# team_back_ECU.net
KiCad netlist of a schematic drawn in Altium Designer
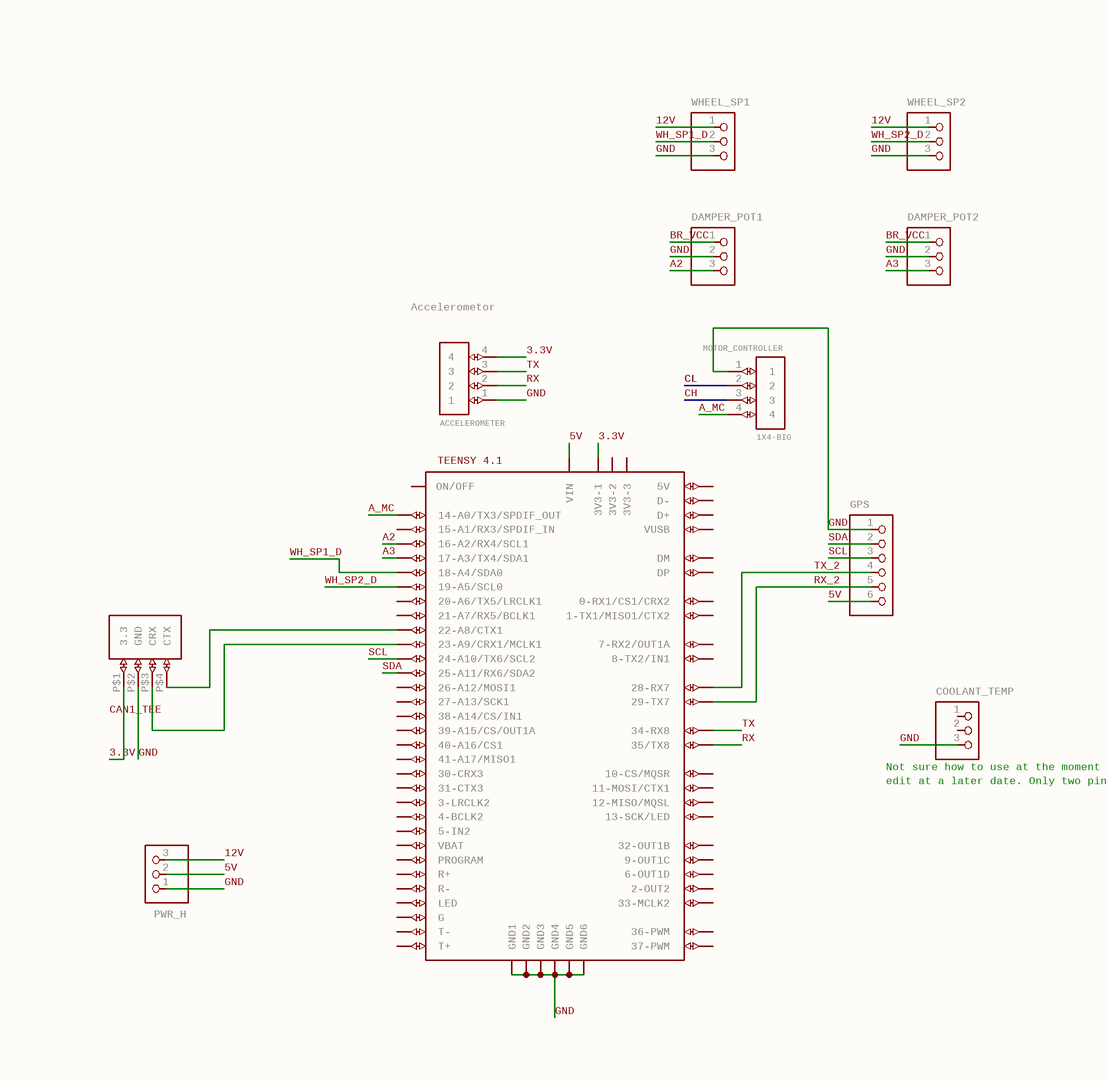
[diagram p0: team back ECU.SchDoc]

(export (version "E")
  (design (tool "Eeschema 10.0.6"))
  (components
    (comp (ref "ACCELEROMETER")
      (value "~")
      (footprint "1X04-3.5MM")
      (description "4-pin connector")
      (fields (field (name "AC") "Accelerometor"))
      (libsource (lib "adafruit") (part "1X4-3.5MM"))
    )
    (comp (ref "CAN1_TEE")
      (value "~")
      (footprint "CAN_TEN")
      (libsource (lib "F-E library custom components") (part "CAN_TEE"))
    )
    (comp (ref "COOLANT_TEMP")
      (value "~")
      (footprint "1X03")
      (description "PIN HEADER")
      (libsource (lib "adafruit") (part "PINHD-1X3"))
    )
    (comp (ref "DAMPER_POT1")
      (value "~")
      (footprint "1X03-CLEANBIG")
      (description "PIN HEADER")
      (libsource (lib "adafruit") (part "PINHD-1X3CB"))
    )
    (comp (ref "DAMPER_POT2")
      (value "~")
      (footprint "1X03-CLEANBIG")
      (description "PIN HEADER")
      (libsource (lib "adafruit") (part "PINHD-1X3CB"))
    )
    (comp (ref "GPS")
      (value "~")
      (footprint "1X06-3.5MM")
      (description "PIN HEADER")
      (libsource (lib "adafruit") (part "PINHD-1X6-3.5MM"))
    )
    (comp (ref "MOTOR_CONTROLLER")
      (value "1X4-BIG")
      (footprint "1X04-BIG")
      (description "4-pin connector")
      (libsource (lib "adafruit") (part "1X4-BIG"))
    )
    (comp (ref "PWR_H")
      (value "~")
      (footprint "1X03")
      (description "PIN HEADER")
      (libsource (lib "adafruit") (part "PINHD-1X3"))
    )
    (comp (ref "U$1")
      (value "~")
      (footprint "TEENSY41")
      (fields (field (name "TEENSY4.1") "TEENSY 4.1"))
      (libsource (lib "teensy") (part "TEENSY41"))
    )
    (comp (ref "WHEEL_SP1")
      (value "~")
      (footprint "1X03")
      (description "PIN HEADER")
      (libsource (lib "adafruit") (part "PINHD-1X3"))
    )
    (comp (ref "WHEEL_SP2")
      (value "~")
      (footprint "1X03")
      (description "PIN HEADER")
      (libsource (lib "adafruit") (part "PINHD-1X3"))
    )
  )
  (nets
    (net (code "3") (name "/3.3V") (class "Default")
      (node (ref "ACCELEROMETER") (pin "4") (pinfunction "4_4") (pintype "bidirectional"))
      (node (ref "CAN1_TEE") (pin "P$1") (pinfunction "3.3_P$1") (pintype "bidirectional"))
      (node (ref "U$1") (pin "3V3-1") (pinfunction "3V3-1_3V3-1") (pintype "bidirectional"))
    )
    (net (code "4") (name "/5V") (class "Default")
      (node (ref "GPS") (pin "6") (pinfunction "6_6") (pintype "passive"))
      (node (ref "PWR_H") (pin "2") (pinfunction "2_2") (pintype "passive"))
      (node (ref "U$1") (pin "VIN") (pinfunction "VIN_VIN") (pintype "bidirectional"))
    )
    (net (code "5") (name "/12V") (class "Default")
      (node (ref "PWR_H") (pin "3") (pinfunction "3_3") (pintype "passive"))
      (node (ref "WHEEL_SP1") (pin "1") (pinfunction "1_1") (pintype "passive"))
      (node (ref "WHEEL_SP2") (pin "1") (pinfunction "1_1") (pintype "passive"))
    )
    (net (code "6") (name "/A2") (class "Default")
      (node (ref "DAMPER_POT1") (pin "3") (pinfunction "3_3") (pintype "passive"))
      (node (ref "U$1") (pin "16-A2/RX4/SCL1") (pinfunction "16-A2/RX4/SCL1_16-A2/RX4/SCL1") (pintype "bidirectional"))
    )
    (net (code "7") (name "/A3") (class "Default")
      (node (ref "DAMPER_POT2") (pin "3") (pinfunction "3_3") (pintype "passive"))
      (node (ref "U$1") (pin "17-A3/TX4/SDA1") (pinfunction "17-A3/TX4/SDA1_17-A3/TX4/SDA1") (pintype "bidirectional"))
    )
    (net (code "8") (name "/A_MC") (class "Default")
      (node (ref "MOTOR_CONTROLLER") (pin "4") (pinfunction "4_4") (pintype "bidirectional"))
      (node (ref "U$1") (pin "14-A0/TX3/SPDIF_OUT") (pinfunction "14-A0/TX3/SPDIF_OUT_14-A0/TX3/SPDIF_OUT") (pintype "bidirectional"))
    )
    (net (code "9") (name "/BR_VCC") (class "Default")
      (node (ref "DAMPER_POT1") (pin "1") (pinfunction "1_1") (pintype "passive"))
      (node (ref "DAMPER_POT2") (pin "1") (pinfunction "1_1") (pintype "passive"))
    )
    (net (code "10") (name "/GND") (class "Default")
      (node (ref "ACCELEROMETER") (pin "1") (pinfunction "1_1") (pintype "bidirectional"))
      (node (ref "CAN1_TEE") (pin "P$2") (pinfunction "GND_P$2") (pintype "bidirectional"))
      (node (ref "COOLANT_TEMP") (pin "3") (pinfunction "3_3") (pintype "passive"))
      (node (ref "DAMPER_POT1") (pin "2") (pinfunction "2_2") (pintype "passive"))
      (node (ref "DAMPER_POT2") (pin "2") (pinfunction "2_2") (pintype "passive"))
      (node (ref "GPS") (pin "1") (pinfunction "1_1") (pintype "passive"))
      (node (ref "MOTOR_CONTROLLER") (pin "1") (pinfunction "1_1") (pintype "bidirectional"))
      (node (ref "PWR_H") (pin "1") (pinfunction "1_1") (pintype "passive"))
      (node (ref "U$1") (pin "GND1") (pinfunction "GND1_GND1") (pintype "bidirectional"))
      (node (ref "U$1") (pin "GND2") (pinfunction "GND2_GND2") (pintype "bidirectional"))
      (node (ref "U$1") (pin "GND3") (pinfunction "GND3_GND3") (pintype "bidirectional"))
      (node (ref "U$1") (pin "GND4") (pinfunction "GND4_GND4") (pintype "bidirectional"))
      (node (ref "U$1") (pin "GND5") (pinfunction "GND5_GND5") (pintype "bidirectional"))
      (node (ref "U$1") (pin "GND6") (pinfunction "GND6_GND6") (pintype "bidirectional"))
      (node (ref "WHEEL_SP1") (pin "3") (pinfunction "3_3") (pintype "passive"))
      (node (ref "WHEEL_SP2") (pin "3") (pinfunction "3_3") (pintype "passive"))
    )
    (net (code "11") (name "/RX") (class "Default")
      (node (ref "ACCELEROMETER") (pin "2") (pinfunction "2_2") (pintype "bidirectional"))
      (node (ref "U$1") (pin "35-TX8") (pinfunction "35/TX8_35-TX8") (pintype "bidirectional"))
    )
    (net (code "12") (name "/RX_2") (class "Default")
      (node (ref "GPS") (pin "5") (pinfunction "5_5") (pintype "passive"))
      (node (ref "U$1") (pin "29-TX7") (pinfunction "29-TX7_29-TX7") (pintype "bidirectional"))
    )
    (net (code "13") (name "/SCL") (class "Default")
      (node (ref "GPS") (pin "3") (pinfunction "3_3") (pintype "passive"))
      (node (ref "U$1") (pin "24-A10/TX6/SCL2") (pinfunction "24-A10/TX6/SCL2_24-A10/TX6/SCL2") (pintype "bidirectional"))
    )
    (net (code "14") (name "/SDA") (class "Default")
      (node (ref "GPS") (pin "2") (pinfunction "2_2") (pintype "passive"))
      (node (ref "U$1") (pin "25-A11/RX6/SDA2") (pinfunction "25-A11/RX6/SDA2_25-A11/RX6/SDA2") (pintype "bidirectional"))
    )
    (net (code "15") (name "/TX") (class "Default")
      (node (ref "ACCELEROMETER") (pin "3") (pinfunction "3_3") (pintype "bidirectional"))
      (node (ref "U$1") (pin "34-RX8") (pinfunction "34-RX8_34-RX8") (pintype "bidirectional"))
    )
    (net (code "16") (name "/TX_2") (class "Default")
      (node (ref "GPS") (pin "4") (pinfunction "4_4") (pintype "passive"))
      (node (ref "U$1") (pin "28-RX7") (pinfunction "28-RX7_28-RX7") (pintype "bidirectional"))
    )
    (net (code "17") (name "/WH_SP1_D") (class "Default")
      (node (ref "U$1") (pin "18-A4/SDA0") (pinfunction "18-A4/SDA0_18-A4/SDA0") (pintype "bidirectional"))
      (node (ref "WHEEL_SP1") (pin "2") (pinfunction "2_2") (pintype "passive"))
    )
    (net (code "18") (name "/WH_SP2_D") (class "Default")
      (node (ref "U$1") (pin "19-A5/SCL0") (pinfunction "19-A5/SCL0_19-A5/SCL0") (pintype "bidirectional"))
      (node (ref "WHEEL_SP2") (pin "2") (pinfunction "2_2") (pintype "passive"))
    )
    (net (code "19") (name "/{CH}") (class "Default")
      (node (ref "MOTOR_CONTROLLER") (pin "3") (pinfunction "3_3") (pintype "bidirectional"))
    )
    (net (code "20") (name "/{CL}") (class "Default")
      (node (ref "MOTOR_CONTROLLER") (pin "2") (pinfunction "2_2") (pintype "bidirectional"))
    )
    (net (code "21") (name "Net-(CAN1_TEE-CRX)") (class "Default")
      (node (ref "CAN1_TEE") (pin "P$3") (pinfunction "CRX_P$3") (pintype "bidirectional"))
      (node (ref "U$1") (pin "23-A9/CRX1/MCLK1") (pinfunction "23-A9/CRX1/MCLK1_23-A9/CRX1/MCLK1") (pintype "bidirectional"))
    )
    (net (code "22") (name "Net-(CAN1_TEE-CTX)") (class "Default")
      (node (ref "CAN1_TEE") (pin "P$4") (pinfunction "CTX_P$4") (pintype "bidirectional"))
      (node (ref "U$1") (pin "22-A8/CTX1") (pinfunction "22-A8/CTX1_22-A8/CTX1") (pintype "bidirectional"))
    )
    (net (code "23") (name "unconnected-(COOLANT_TEMP-Pad1)") (class "Default")
      (node (ref "COOLANT_TEMP") (pin "1") (pinfunction "1_1") (pintype "passive"))
    )
    (net (code "24") (name "unconnected-(COOLANT_TEMP-Pad2)") (class "Default")
      (node (ref "COOLANT_TEMP") (pin "2") (pinfunction "2_2") (pintype "passive"))
    )
    (net (code "25") (name "unconnected-(U$1-5V-Pad+5V)") (class "Default")
      (node (ref "U$1") (pin "+5V") (pinfunction "5V_+5V") (pintype "bidirectional"))
    )
    (net (code "26") (name "unconnected-(U$1-8-TX2{slash}IN1-Pad8-TX2{slash}IN2)") (class "Default")
      (node (ref "U$1") (pin "8-TX2/IN2") (pinfunction "8-TX2/IN1_8-TX2/IN2") (pintype "bidirectional"))
    )
    (net (code "27") (name "unconnected-(U$1-10-CS{slash}MQSR-Pad10-C~{S}MQSR)") (class "Default")
      (node (ref "U$1") (pin "10-C~{S}MQSR") (pinfunction "10-CS/MQSR_10-C~{S}MQSR") (pintype "bidirectional"))
    )
    (net (code "28") (name "unconnected-(U$1-Pad0-RX1{slash}CS1{slash}CRX2)") (class "Default")
      (node (ref "U$1") (pin "0-RX1/CS1/CRX2") (pinfunction "0-RX1/CS1/CRX2_0-RX1/CS1/CRX2") (pintype "bidirectional"))
    )
    (net (code "29") (name "unconnected-(U$1-Pad1-TX1{slash}MISO1{slash}CTX2)") (class "Default")
      (node (ref "U$1") (pin "1-TX1/MISO1/CTX2") (pinfunction "1-TX1/MISO1/CTX2_1-TX1/MISO1/CTX2") (pintype "bidirectional"))
    )
    (net (code "30") (name "unconnected-(U$1-Pad2-OUT2)") (class "Default")
      (node (ref "U$1") (pin "2-OUT2") (pinfunction "2-OUT2_2-OUT2") (pintype "bidirectional"))
    )
    (net (code "31") (name "unconnected-(U$1-Pad3-LRCLK2)") (class "Default")
      (node (ref "U$1") (pin "3-LRCLK2") (pinfunction "3-LRCLK2_3-LRCLK2") (pintype "bidirectional"))
    )
    (net (code "32") (name "unconnected-(U$1-Pad3V3-2)") (class "Default")
      (node (ref "U$1") (pin "3V3-2") (pinfunction "3V3-2_3V3-2") (pintype "bidirectional"))
    )
    (net (code "33") (name "unconnected-(U$1-Pad3V3-3)") (class "Default")
      (node (ref "U$1") (pin "3V3-3") (pinfunction "3V3-3_3V3-3") (pintype "bidirectional"))
    )
    (net (code "34") (name "unconnected-(U$1-Pad4-BCLK2)") (class "Default")
      (node (ref "U$1") (pin "4-BCLK2") (pinfunction "4-BCLK2_4-BCLK2") (pintype "bidirectional"))
    )
    (net (code "35") (name "unconnected-(U$1-Pad5-IN2)") (class "Default")
      (node (ref "U$1") (pin "5-IN2") (pinfunction "5-IN2_5-IN2") (pintype "bidirectional"))
    )
    (net (code "36") (name "unconnected-(U$1-Pad6-OUT1D)") (class "Default")
      (node (ref "U$1") (pin "6-OUT1D") (pinfunction "6-OUT1D_6-OUT1D") (pintype "bidirectional"))
    )
    (net (code "37") (name "unconnected-(U$1-Pad7-RX2{slash}OUT1A)") (class "Default")
      (node (ref "U$1") (pin "7-RX2/OUT1A") (pinfunction "7-RX2/OUT1A_7-RX2/OUT1A") (pintype "bidirectional"))
    )
    (net (code "38") (name "unconnected-(U$1-Pad9-OUT1C)") (class "Default")
      (node (ref "U$1") (pin "9-OUT1C") (pinfunction "9-OUT1C_9-OUT1C") (pintype "bidirectional"))
    )
    (net (code "39") (name "unconnected-(U$1-Pad11-MOSI{slash}CTX1)") (class "Default")
      (node (ref "U$1") (pin "11-MOSI/CTX1") (pinfunction "11-MOSI/CTX1_11-MOSI/CTX1") (pintype "bidirectional"))
    )
    (net (code "40") (name "unconnected-(U$1-Pad12-MISO{slash}MQSL)") (class "Default")
      (node (ref "U$1") (pin "12-MISO/MQSL") (pinfunction "12-MISO/MQSL_12-MISO/MQSL") (pintype "bidirectional"))
    )
    (net (code "41") (name "unconnected-(U$1-Pad13-SCK{slash}LED)") (class "Default")
      (node (ref "U$1") (pin "13-SCK/LED") (pinfunction "13-SCK/LED_13-SCK/LED") (pintype "bidirectional"))
    )
    (net (code "42") (name "unconnected-(U$1-Pad15-A1{slash}RX3{slash}SPDIF_IN)") (class "Default")
      (node (ref "U$1") (pin "15-A1/RX3/SPDIF_IN") (pinfunction "15-A1/RX3/SPDIF_IN_15-A1/RX3/SPDIF_IN") (pintype "bidirectional"))
    )
    (net (code "43") (name "unconnected-(U$1-Pad20-A6{slash}TX5{slash}LRCLK1)") (class "Default")
      (node (ref "U$1") (pin "20-A6/TX5/LRCLK1") (pinfunction "20-A6/TX5/LRCLK1_20-A6/TX5/LRCLK1") (pintype "bidirectional"))
    )
    (net (code "44") (name "unconnected-(U$1-Pad21-A7{slash}RX5{slash}BCLK1)") (class "Default")
      (node (ref "U$1") (pin "21-A7/RX5/BCLK1") (pinfunction "21-A7/RX5/BCLK1_21-A7/RX5/BCLK1") (pintype "bidirectional"))
    )
    (net (code "45") (name "unconnected-(U$1-Pad26-A12{slash}MOSI1)") (class "Default")
      (node (ref "U$1") (pin "26-A12/MOSI1") (pinfunction "26-A12/MOSI1_26-A12/MOSI1") (pintype "bidirectional"))
    )
    (net (code "46") (name "unconnected-(U$1-Pad27-A13{slash}SCK1)") (class "Default")
      (node (ref "U$1") (pin "27-A13/SCK1") (pinfunction "27-A13/SCK1_27-A13/SCK1") (pintype "bidirectional"))
    )
    (net (code "47") (name "unconnected-(U$1-Pad30-CRX3)") (class "Default")
      (node (ref "U$1") (pin "30-CRX3") (pinfunction "30-CRX3_30-CRX3") (pintype "bidirectional"))
    )
    (net (code "48") (name "unconnected-(U$1-Pad31-CTX3)") (class "Default")
      (node (ref "U$1") (pin "31-CTX3") (pinfunction "31-CTX3_31-CTX3") (pintype "bidirectional"))
    )
    (net (code "49") (name "unconnected-(U$1-Pad32-OUT1B)") (class "Default")
      (node (ref "U$1") (pin "32-OUT1B") (pinfunction "32-OUT1B_32-OUT1B") (pintype "bidirectional"))
    )
    (net (code "50") (name "unconnected-(U$1-Pad33-MCLK2)") (class "Default")
      (node (ref "U$1") (pin "33-MCLK2") (pinfunction "33-MCLK2_33-MCLK2") (pintype "bidirectional"))
    )
    (net (code "51") (name "unconnected-(U$1-Pad36-PWM)") (class "Default")
      (node (ref "U$1") (pin "36-PWM") (pinfunction "36-PWM_36-PWM") (pintype "bidirectional"))
    )
    (net (code "52") (name "unconnected-(U$1-Pad37-PWM)") (class "Default")
      (node (ref "U$1") (pin "37-PWM") (pinfunction "37-PWM_37-PWM") (pintype "bidirectional"))
    )
    (net (code "53") (name "unconnected-(U$1-Pad38-A14{slash}CS{slash}IN1)") (class "Default")
      (node (ref "U$1") (pin "38-A14/CS/IN1") (pinfunction "38-A14/CS/IN1_38-A14/CS/IN1") (pintype "bidirectional"))
    )
    (net (code "54") (name "unconnected-(U$1-Pad39-A15{slash}CS{slash}OUT1A)") (class "Default")
      (node (ref "U$1") (pin "39-A15/CS/OUT1A") (pinfunction "39-A15/CS/OUT1A_39-A15/CS/OUT1A") (pintype "bidirectional"))
    )
    (net (code "55") (name "unconnected-(U$1-Pad40-A16{slash}CS1)") (class "Default")
      (node (ref "U$1") (pin "40-A16/CS1") (pinfunction "40-A16/CS1_40-A16/CS1") (pintype "bidirectional"))
    )
    (net (code "56") (name "unconnected-(U$1-Pad41-A17{slash}MISO1)") (class "Default")
      (node (ref "U$1") (pin "41-A17/MISO1") (pinfunction "41-A17/MISO1_41-A17/MISO1") (pintype "bidirectional"))
    )
    (net (code "57") (name "unconnected-(U$1-PadD+)") (class "Default")
      (node (ref "U$1") (pin "D+") (pinfunction "D+_D+") (pintype "bidirectional"))
    )
    (net (code "58") (name "unconnected-(U$1-PadD-)") (class "Default")
      (node (ref "U$1") (pin "D-") (pinfunction "D-_D-") (pintype "bidirectional"))
    )
    (net (code "59") (name "unconnected-(U$1-PadDM)") (class "Default")
      (node (ref "U$1") (pin "DM") (pinfunction "DM_DM") (pintype "bidirectional"))
    )
    (net (code "60") (name "unconnected-(U$1-PadDP)") (class "Default")
      (node (ref "U$1") (pin "DP") (pinfunction "DP_DP") (pintype "bidirectional"))
    )
    (net (code "61") (name "unconnected-(U$1-PadG)") (class "Default")
      (node (ref "U$1") (pin "G") (pinfunction "G_G") (pintype "bidirectional"))
    )
    (net (code "62") (name "unconnected-(U$1-PadLED)") (class "Default")
      (node (ref "U$1") (pin "LED") (pinfunction "LED_LED") (pintype "bidirectional"))
    )
    (net (code "63") (name "unconnected-(U$1-PadON{slash}OFF)") (class "Default")
      (node (ref "U$1") (pin "ON/OFF") (pinfunction "ON/OFF_ON/OFF") (pintype "bidirectional"))
    )
    (net (code "64") (name "unconnected-(U$1-PadPROGRAM)") (class "Default")
      (node (ref "U$1") (pin "PROGRAM") (pinfunction "PROGRAM_PROGRAM") (pintype "bidirectional"))
    )
    (net (code "65") (name "unconnected-(U$1-PadR+)") (class "Default")
      (node (ref "U$1") (pin "R+") (pinfunction "R+_R+") (pintype "bidirectional"))
    )
    (net (code "66") (name "unconnected-(U$1-PadR-)") (class "Default")
      (node (ref "U$1") (pin "R-") (pinfunction "R-_R-") (pintype "bidirectional"))
    )
    (net (code "67") (name "unconnected-(U$1-PadT+)") (class "Default")
      (node (ref "U$1") (pin "T+") (pinfunction "T+_T+") (pintype "bidirectional"))
    )
    (net (code "68") (name "unconnected-(U$1-PadT-)") (class "Default")
      (node (ref "U$1") (pin "T-") (pinfunction "T-_T-") (pintype "bidirectional"))
    )
    (net (code "69") (name "unconnected-(U$1-PadVBAT)") (class "Default")
      (node (ref "U$1") (pin "VBAT") (pinfunction "VBAT_VBAT") (pintype "bidirectional"))
    )
    (net (code "70") (name "unconnected-(U$1-PadVUSB)") (class "Default")
      (node (ref "U$1") (pin "VUSB") (pinfunction "VUSB_VUSB") (pintype "bidirectional"))
    )
  )
)
